# Spolerigg2.net
KiCad netlist of a schematic drawn in Altium Designer
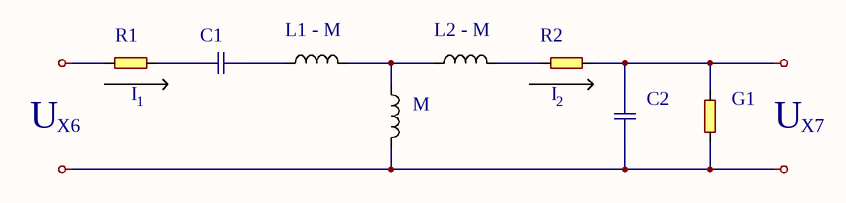
[diagram p0: Spolerigg2.SchDoc]

(export (version "E")
  (design (tool "Eeschema 10.0.6"))
  (components
    (comp (ref "C1")
      (value "PC/HV/S/WF 22NF")
      (footprint "CAPAD340W1L280D11B")
      (description "CAP, FILM, PP, 22NF, 1.5KV, AXIAL")
      (libsource (lib "OVLib") (part "CAP"))
    )
    (comp (ref "C2")
      (value "PC/HV/S/WF 22NF")
      (footprint "CAPAD340W1L280D11B")
      (description "CAP, FILM, PP, 22NF, 1.5KV, AXIAL")
      (libsource (lib "OVLib") (part "CAP"))
    )
    (comp (ref "G1")
      (value "1.0")
      (footprint "RESA_0.25W")
      (description "0.25W 1% Generic resistor")
      (libsource (lib "") (part "Resistor2_1"))
    )
    (comp (ref "L1 - M")
      (value "SMD spoler")
      (footprint "INDP3225X20N")
      (description "SMD inductors og tomme SMD bokser")
      (libsource (lib "OVLib") (part "IND_GENERIC"))
    )
    (comp (ref "L2 - M")
      (value "SMD spoler")
      (footprint "INDP3225X20N")
      (description "SMD inductors og tomme SMD bokser")
      (libsource (lib "OVLib") (part "IND_GENERIC"))
    )
    (comp (ref "M")
      (value "SMD spoler")
      (footprint "INDP3225X20N")
      (description "SMD inductors og tomme SMD bokser")
      (libsource (lib "OVLib") (part "IND_GENERIC"))
    )
    (comp (ref "R1")
      (value "1.0")
      (footprint "RESA_0.25W")
      (description "0.25W 1% Generic resistor")
      (libsource (lib "OVLib") (part "Resistor2"))
    )
    (comp (ref "R2")
      (value "1.0")
      (footprint "RESA_0.25W")
      (description "0.25W 1% Generic resistor")
      (libsource (lib "OVLib") (part "Resistor2"))
    )
  )
  (nets
    (net (code "1") (name "GND") (class "Default")
      (node (ref "C2") (pin "1") (pinfunction "1_1") (pintype "passive"))
      (node (ref "G1") (pin "1") (pinfunction "1_1") (pintype "passive"))
      (node (ref "M") (pin "2") (pinfunction "2_2") (pintype "passive"))
    )
    (net (code "2") (name "IN") (class "Default")
      (node (ref "R1") (pin "1") (pinfunction "1_1") (pintype "passive"))
    )
    (net (code "3") (name "Net-(C1-Pad1)") (class "Default")
      (node (ref "C1") (pin "1") (pinfunction "1_1") (pintype "passive"))
      (node (ref "R1") (pin "2") (pinfunction "2_2") (pintype "passive"))
    )
    (net (code "4") (name "Net-(C1-Pad2)") (class "Default")
      (node (ref "C1") (pin "2") (pinfunction "2_2") (pintype "passive"))
      (node (ref "L1 - M") (pin "1") (pinfunction "1_1") (pintype "passive"))
    )
    (net (code "5") (name "Net-(L1 - M-Pad2)") (class "Default")
      (node (ref "L1 - M") (pin "2") (pinfunction "2_2") (pintype "passive"))
      (node (ref "L2 - M") (pin "1") (pinfunction "1_1") (pintype "passive"))
      (node (ref "M") (pin "1") (pinfunction "1_1") (pintype "passive"))
    )
    (net (code "6") (name "Net-(L2 - M-Pad2)") (class "Default")
      (node (ref "L2 - M") (pin "2") (pinfunction "2_2") (pintype "passive"))
      (node (ref "R2") (pin "1") (pinfunction "1_1") (pintype "passive"))
    )
    (net (code "7") (name "OUT") (class "Default")
      (node (ref "C2") (pin "2") (pinfunction "2_2") (pintype "passive"))
      (node (ref "G1") (pin "2") (pinfunction "2_2") (pintype "passive"))
      (node (ref "R2") (pin "2") (pinfunction "2_2") (pintype "passive"))
    )
  )
)
